# dio_pmod.net
KiCad netlist of a schematic drawn in EAGLE
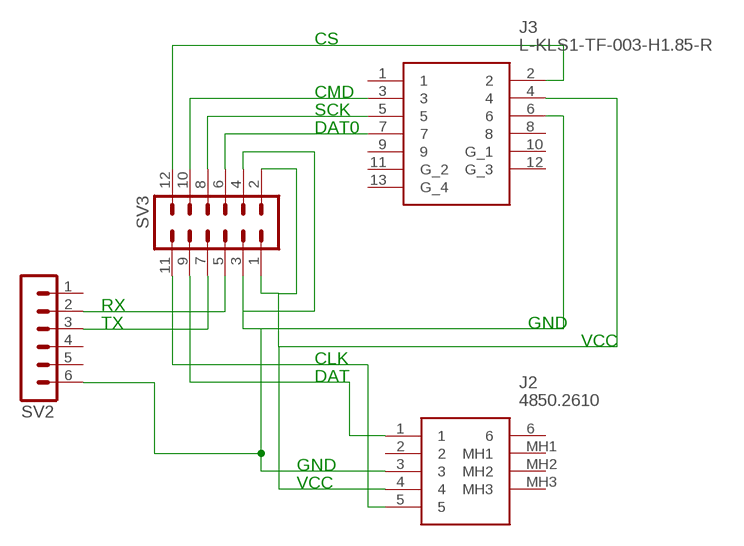
[diagram p0: schematic, sheet 1]

(export (version "E")
  (design (tool "Eeschema 10.0.6"))
  (components
    (comp (ref "J2")
      (value "4850.2610")
      (footprint "eagle-import:48502610")
      (fields (field (name "MOUSER_PART_NUMBER") "693-4850.2610"))
      (libsource (lib "eagle-import") (part "4850.2610"))
    )
    (comp (ref "J3")
      (value "L-KLS1-TF-003-H1.85-R")
      (footprint "eagle-import:L-KLS1-TF-003-H1.85-R")
      (libsource (lib "eagle-import") (part "L-KLS1-TF-003-H1.85-R"))
    )
    (comp (ref "SV2")
      (value "MA06-1")
      (footprint "eagle-import:MA06-1")
      (libsource (lib "eagle-import") (part "MA06-1"))
    )
    (comp (ref "SV3")
      (value "MA06-2")
      (footprint "eagle-import:MA06-2")
      (libsource (lib "eagle-import") (part "MA06-2"))
    )
  )
  (nets
    (net (code "1") (name "Net-(J2-Pad1)") (class "Default")
      (node (ref "J2") (pin "1") (pinfunction "1_1") (pintype "bidirectional"))
      (node (ref "SV3") (pin "9") (pinfunction "9_9") (pintype "passive"))
    )
    (net (code "2") (name "Net-(J2-Pad3)") (class "Default")
      (node (ref "J2") (pin "3") (pinfunction "3_3") (pintype "bidirectional"))
      (node (ref "J3") (pin "6") (pinfunction "6_6") (pintype "bidirectional"))
      (node (ref "SV2") (pin "6") (pinfunction "6_6") (pintype "passive"))
      (node (ref "SV3") (pin "3") (pinfunction "3_3") (pintype "passive"))
      (node (ref "SV3") (pin "4") (pinfunction "4_4") (pintype "passive"))
    )
    (net (code "3") (name "Net-(J2-Pad4)") (class "Default")
      (node (ref "J2") (pin "4") (pinfunction "4_4") (pintype "bidirectional"))
      (node (ref "J3") (pin "4") (pinfunction "4_4") (pintype "bidirectional"))
      (node (ref "SV3") (pin "1") (pinfunction "1_1") (pintype "passive"))
      (node (ref "SV3") (pin "2") (pinfunction "2_2") (pintype "passive"))
    )
    (net (code "4") (name "Net-(J2-Pad5)") (class "Default")
      (node (ref "J2") (pin "5") (pinfunction "5_5") (pintype "bidirectional"))
      (node (ref "SV3") (pin "11") (pinfunction "11_11") (pintype "passive"))
    )
    (net (code "5") (name "Net-(J3-Pad2)") (class "Default")
      (node (ref "J3") (pin "2") (pinfunction "2_2") (pintype "bidirectional"))
      (node (ref "SV3") (pin "12") (pinfunction "12_12") (pintype "passive"))
    )
    (net (code "6") (name "Net-(J3-Pad3)") (class "Default")
      (node (ref "J3") (pin "3") (pinfunction "3_3") (pintype "bidirectional"))
      (node (ref "SV3") (pin "10") (pinfunction "10_10") (pintype "passive"))
    )
    (net (code "7") (name "Net-(J3-Pad5)") (class "Default")
      (node (ref "J3") (pin "5") (pinfunction "5_5") (pintype "bidirectional"))
      (node (ref "SV3") (pin "8") (pinfunction "8_8") (pintype "passive"))
    )
    (net (code "8") (name "Net-(J3-Pad7)") (class "Default")
      (node (ref "J3") (pin "7") (pinfunction "7_7") (pintype "bidirectional"))
      (node (ref "SV3") (pin "6") (pinfunction "6_6") (pintype "passive"))
    )
    (net (code "9") (name "Net-(SV2-Pad2)") (class "Default")
      (node (ref "SV2") (pin "2") (pinfunction "2_2") (pintype "passive"))
      (node (ref "SV3") (pin "5") (pinfunction "5_5") (pintype "passive"))
    )
    (net (code "10") (name "Net-(SV2-Pad3)") (class "Default")
      (node (ref "SV2") (pin "3") (pinfunction "3_3") (pintype "passive"))
      (node (ref "SV3") (pin "7") (pinfunction "7_7") (pintype "passive"))
    )
    (net (code "11") (name "unconnected-(J2-Pad2)") (class "Default")
      (node (ref "J2") (pin "2") (pinfunction "2_2") (pintype "bidirectional"))
    )
    (net (code "12") (name "unconnected-(J2-Pad6)") (class "Default")
      (node (ref "J2") (pin "6") (pinfunction "6_6") (pintype "bidirectional"))
    )
    (net (code "13") (name "unconnected-(J2-PadMH1)") (class "Default")
      (node (ref "J2") (pin "MH1") (pinfunction "MH1_MH1") (pintype "bidirectional"))
    )
    (net (code "14") (name "unconnected-(J2-PadMH2)") (class "Default")
      (node (ref "J2") (pin "MH2") (pinfunction "MH2_MH2") (pintype "bidirectional"))
    )
    (net (code "15") (name "unconnected-(J2-PadMH3)") (class "Default")
      (node (ref "J2") (pin "MH3") (pinfunction "MH3_MH3") (pintype "bidirectional"))
    )
    (net (code "16") (name "unconnected-(J3-G_1-Pad10)") (class "Default")
      (node (ref "J3") (pin "10") (pinfunction "G_1_10") (pintype "bidirectional"))
    )
    (net (code "17") (name "unconnected-(J3-G_2-Pad11)") (class "Default")
      (node (ref "J3") (pin "11") (pinfunction "G_2_11") (pintype "bidirectional"))
    )
    (net (code "18") (name "unconnected-(J3-G_3-Pad12)") (class "Default")
      (node (ref "J3") (pin "12") (pinfunction "G_3_12") (pintype "bidirectional"))
    )
    (net (code "19") (name "unconnected-(J3-G_4-Pad13)") (class "Default")
      (node (ref "J3") (pin "13") (pinfunction "G_4_13") (pintype "bidirectional"))
    )
    (net (code "20") (name "unconnected-(J3-Pad1)") (class "Default")
      (node (ref "J3") (pin "1") (pinfunction "1_1") (pintype "bidirectional"))
    )
    (net (code "21") (name "unconnected-(J3-Pad8)") (class "Default")
      (node (ref "J3") (pin "8") (pinfunction "8_8") (pintype "bidirectional"))
    )
    (net (code "22") (name "unconnected-(J3-Pad9)") (class "Default")
      (node (ref "J3") (pin "9") (pinfunction "9_9") (pintype "bidirectional"))
    )
    (net (code "23") (name "unconnected-(SV2-Pad1)") (class "Default")
      (node (ref "SV2") (pin "1") (pinfunction "1_1") (pintype "passive"))
    )
    (net (code "24") (name "unconnected-(SV2-Pad4)") (class "Default")
      (node (ref "SV2") (pin "4") (pinfunction "4_4") (pintype "passive"))
    )
    (net (code "25") (name "unconnected-(SV2-Pad5)") (class "Default")
      (node (ref "SV2") (pin "5") (pinfunction "5_5") (pintype "passive"))
    )
  )
)
